# commu.net
KiCad netlist of a schematic drawn in Altium Designer
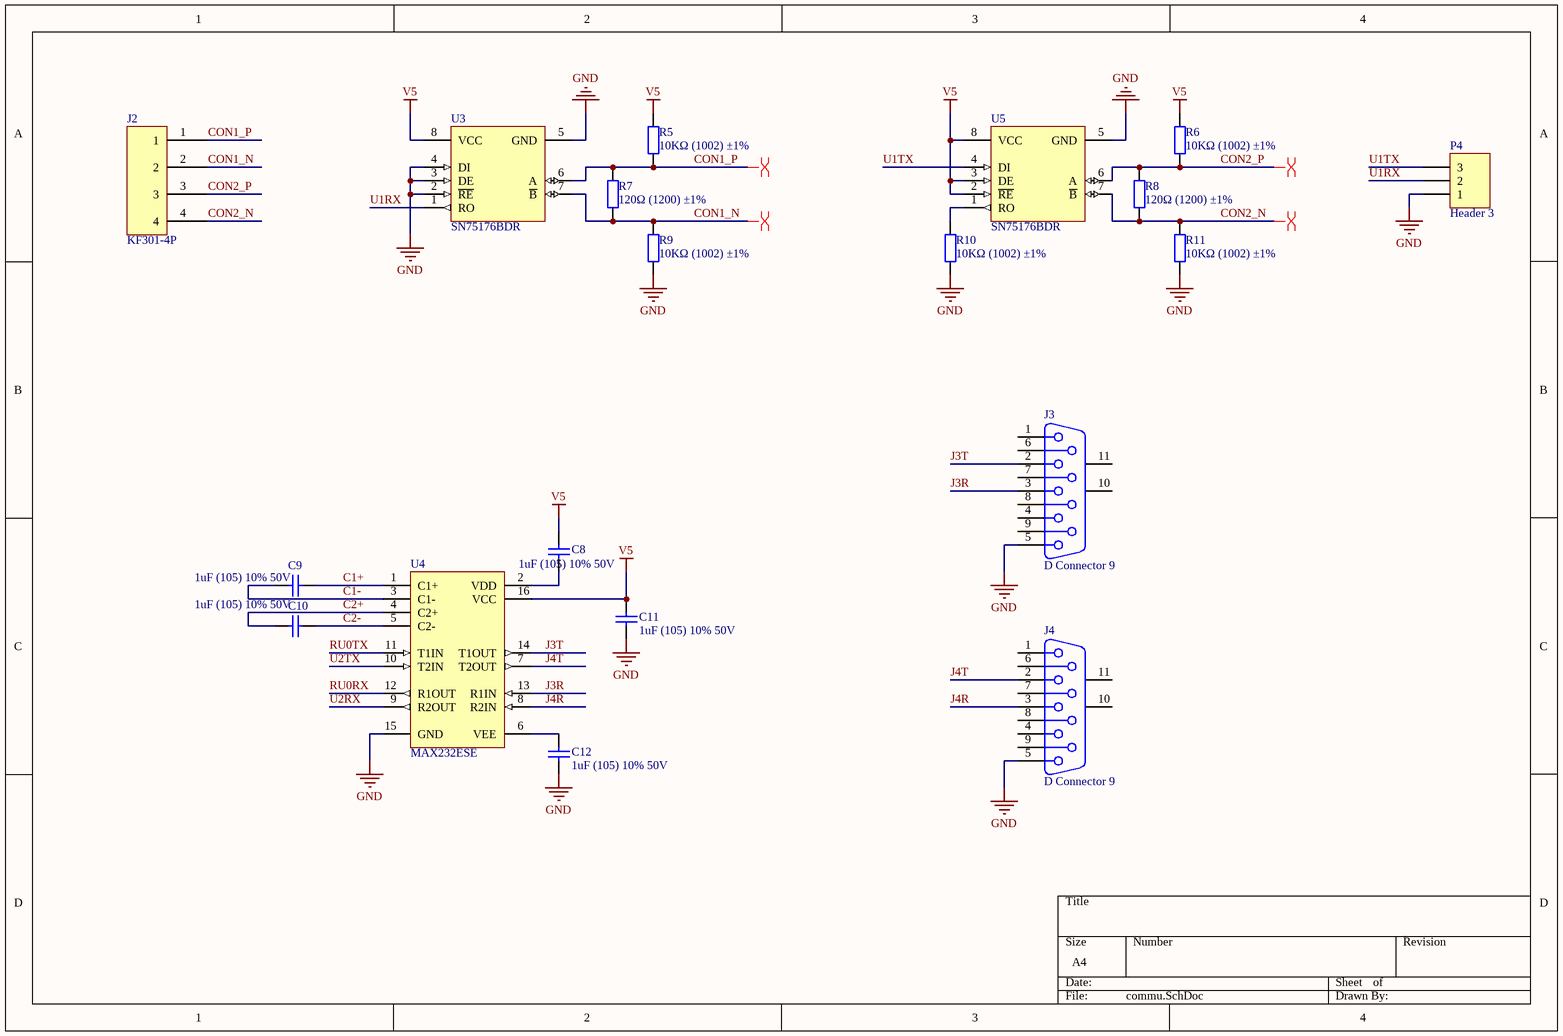
[diagram p0: commu.SchDoc]

(export (version "E")
  (design (tool "Eeschema 10.0.6"))
  (components
    (comp (ref "C8")
      (value "1uF (105) 10% 50V")
      (footprint "0603_C")
      (description "贴片电容")
      (libsource (lib "Miscellaneous Devices LC") (part "0603 1uF (105) 10% 50V"))
    )
    (comp (ref "C9")
      (value "1uF (105) 10% 50V")
      (footprint "0603_C")
      (description "贴片电容")
      (libsource (lib "Miscellaneous Devices LC") (part "0603 1uF (105) 10% 50V"))
    )
    (comp (ref "C10")
      (value "1uF (105) 10% 50V")
      (footprint "0603_C")
      (description "贴片电容")
      (libsource (lib "Miscellaneous Devices LC") (part "0603 1uF (105) 10% 50V"))
    )
    (comp (ref "C11")
      (value "1uF (105) 10% 50V")
      (footprint "0603_C")
      (description "贴片电容")
      (libsource (lib "Miscellaneous Devices LC") (part "0603 1uF (105) 10% 50V"))
    )
    (comp (ref "C12")
      (value "1uF (105) 10% 50V")
      (footprint "0603_C")
      (description "贴片电容")
      (libsource (lib "Miscellaneous Devices LC") (part "0603 1uF (105) 10% 50V"))
    )
    (comp (ref "J2") (value "KF301-4P") (footprint "KF301-4P") (libsource (lib "CHK-I") (part "KF301-4P")))
    (comp (ref "J3")
      (value "D Connector 9")
      (footprint "DSUB1.385-2H9")
      (description "Receptacle Assembly, 9 Position, Right Angle")
      (fields (field (name "PUBLISHER") "Altium Limited"))
      (libsource (lib "Miscellaneous Connectors") (part "D Connector 9"))
    )
    (comp (ref "J4")
      (value "D Connector 9")
      (footprint "DSUB1.385-2H9")
      (description "Receptacle Assembly, 9 Position, Right Angle")
      (fields (field (name "PUBLISHER") "Altium Limited"))
      (libsource (lib "Miscellaneous Connectors") (part "D Connector 9"))
    )
    (comp (ref "P4")
      (value "Header 3")
      (footprint "HDR1X3")
      (description "Header, 3-Pin")
      (fields (field (name "PUBLISHER") "Altium Limited"))
      (libsource (lib "Miscellaneous Connectors") (part "Header 3"))
    )
    (comp (ref "R5")
      (value "10KΩ (1002) ±1%")
      (footprint "0603_R")
      (description "贴片电阻")
      (libsource (lib "Miscellaneous Devices LC") (part "0603 10KΩ (1002) 1%"))
    )
    (comp (ref "R6")
      (value "10KΩ (1002) ±1%")
      (footprint "0603_R")
      (description "贴片电阻")
      (libsource (lib "Miscellaneous Devices LC") (part "0603 10KΩ (1002) 1%"))
    )
    (comp (ref "R7")
      (value "120Ω (1200) ±1%")
      (footprint "0603_R")
      (description "贴片电阻")
      (libsource (lib "Miscellaneous Devices LC") (part "0603 120Ω (1200) 1%"))
    )
    (comp (ref "R8")
      (value "120Ω (1200) ±1%")
      (footprint "0603_R")
      (description "贴片电阻")
      (libsource (lib "Miscellaneous Devices LC") (part "0603 120Ω (1200) 1%"))
    )
    (comp (ref "R9")
      (value "10KΩ (1002) ±1%")
      (footprint "0603_R")
      (description "贴片电阻")
      (libsource (lib "Miscellaneous Devices LC") (part "0603 10KΩ (1002) 1%"))
    )
    (comp (ref "R10")
      (value "10KΩ (1002) ±1%")
      (footprint "0603_R")
      (description "贴片电阻")
      (libsource (lib "Miscellaneous Devices LC") (part "0603 10KΩ (1002) 1%"))
    )
    (comp (ref "R11")
      (value "10KΩ (1002) ±1%")
      (footprint "0603_R")
      (description "贴片电阻")
      (libsource (lib "Miscellaneous Devices LC") (part "0603 10KΩ (1002) 1%"))
    )
    (comp (ref "U3")
      (value "SN75176BDR")
      (footprint "SOIC-8_150mil")
      (description "RS-485/RS-422")
      (libsource (lib "Miscellaneous Devices LC") (part "SN75176BDR_[C7063]"))
    )
    (comp (ref "U4")
      (value "MAX232ESE")
      (footprint "SOIC-16_150mil")
      (description "RS232")
      (libsource (lib "Miscellaneous Devices LC") (part "MAX232ESE_[C26860]"))
    )
    (comp (ref "U5")
      (value "SN75176BDR")
      (footprint "SOIC-8_150mil")
      (description "RS-485/RS-422")
      (libsource (lib "Miscellaneous Devices LC") (part "SN75176BDR_[C7063]"))
    )
  )
  (nets
    (net (code "1") (name "/C1+") (class "Default")
      (node (ref "C9") (pin "2") (pinfunction "2_2") (pintype "passive"))
      (node (ref "U4") (pin "1") (pinfunction "C1+_1") (pintype "passive"))
    )
    (net (code "2") (name "/C1-") (class "Default")
      (node (ref "C9") (pin "1") (pinfunction "1_1") (pintype "passive"))
      (node (ref "U4") (pin "3") (pinfunction "C1-_3") (pintype "passive"))
    )
    (net (code "3") (name "/C2+") (class "Default")
      (node (ref "C10") (pin "1") (pinfunction "1_1") (pintype "passive"))
      (node (ref "U4") (pin "4") (pinfunction "C2+_4") (pintype "passive"))
    )
    (net (code "4") (name "/C2-") (class "Default")
      (node (ref "C10") (pin "2") (pinfunction "2_2") (pintype "passive"))
      (node (ref "U4") (pin "5") (pinfunction "C2-_5") (pintype "passive"))
    )
    (net (code "5") (name "/CON1_N") (class "Default")
      (node (ref "J2") (pin "2") (pinfunction "2_2") (pintype "passive"))
      (node (ref "R7") (pin "1") (pinfunction "1_1") (pintype "passive"))
      (node (ref "R9") (pin "2") (pinfunction "2_2") (pintype "passive"))
      (node (ref "U3") (pin "7") (pinfunction "~{B}_7") (pintype "bidirectional"))
    )
    (net (code "6") (name "/CON1_P") (class "Default")
      (node (ref "J2") (pin "1") (pinfunction "1_1") (pintype "passive"))
      (node (ref "R5") (pin "1") (pinfunction "1_1") (pintype "passive"))
      (node (ref "R7") (pin "2") (pinfunction "2_2") (pintype "passive"))
      (node (ref "U3") (pin "6") (pinfunction "A_6") (pintype "bidirectional"))
    )
    (net (code "7") (name "/CON2_N") (class "Default")
      (node (ref "J2") (pin "4") (pinfunction "4_4") (pintype "passive"))
      (node (ref "R11") (pin "2") (pinfunction "2_2") (pintype "passive"))
      (node (ref "R8") (pin "1") (pinfunction "1_1") (pintype "passive"))
      (node (ref "U5") (pin "7") (pinfunction "~{B}_7") (pintype "bidirectional"))
    )
    (net (code "8") (name "/CON2_P") (class "Default")
      (node (ref "J2") (pin "3") (pinfunction "3_3") (pintype "passive"))
      (node (ref "R6") (pin "1") (pinfunction "1_1") (pintype "passive"))
      (node (ref "R8") (pin "2") (pinfunction "2_2") (pintype "passive"))
      (node (ref "U5") (pin "6") (pinfunction "A_6") (pintype "bidirectional"))
    )
    (net (code "9") (name "/J3R") (class "Default")
      (node (ref "J3") (pin "3") (pinfunction "3_3") (pintype "passive"))
      (node (ref "U4") (pin "13") (pinfunction "R1IN_13") (pintype "input"))
    )
    (net (code "10") (name "/J3T") (class "Default")
      (node (ref "J3") (pin "2") (pinfunction "2_2") (pintype "passive"))
      (node (ref "U4") (pin "14") (pinfunction "T1OUT_14") (pintype "output"))
    )
    (net (code "11") (name "/J4R") (class "Default")
      (node (ref "J4") (pin "3") (pinfunction "3_3") (pintype "passive"))
      (node (ref "U4") (pin "8") (pinfunction "R2IN_8") (pintype "input"))
    )
    (net (code "12") (name "/J4T") (class "Default")
      (node (ref "J4") (pin "2") (pinfunction "2_2") (pintype "passive"))
      (node (ref "U4") (pin "7") (pinfunction "T2OUT_7") (pintype "output"))
    )
    (net (code "13") (name "/RU0RX") (class "Default")
      (node (ref "U4") (pin "12") (pinfunction "R1OUT_12") (pintype "output"))
    )
    (net (code "14") (name "/RU0TX") (class "Default")
      (node (ref "U4") (pin "11") (pinfunction "T1IN_11") (pintype "input"))
    )
    (net (code "15") (name "/U1RX") (class "Default")
      (node (ref "P4") (pin "2") (pinfunction "2_2") (pintype "passive"))
      (node (ref "U3") (pin "1") (pinfunction "RO_1") (pintype "output"))
    )
    (net (code "16") (name "/U1TX") (class "Default")
      (node (ref "P4") (pin "3") (pinfunction "3_3") (pintype "passive"))
      (node (ref "U5") (pin "4") (pinfunction "DI_4") (pintype "input"))
    )
    (net (code "17") (name "/U2RX") (class "Default")
      (node (ref "U4") (pin "9") (pinfunction "R2OUT_9") (pintype "output"))
    )
    (net (code "18") (name "/U2TX") (class "Default")
      (node (ref "U4") (pin "10") (pinfunction "T2IN_10") (pintype "input"))
    )
    (net (code "19") (name "GND") (class "Default")
      (node (ref "C11") (pin "1") (pinfunction "1_1") (pintype "passive"))
      (node (ref "C12") (pin "1") (pinfunction "1_1") (pintype "passive"))
      (node (ref "J3") (pin "5") (pinfunction "5_5") (pintype "passive"))
      (node (ref "J4") (pin "5") (pinfunction "5_5") (pintype "passive"))
      (node (ref "P4") (pin "1") (pinfunction "1_1") (pintype "passive"))
      (node (ref "R10") (pin "1") (pinfunction "1_1") (pintype "passive"))
      (node (ref "R11") (pin "1") (pinfunction "1_1") (pintype "passive"))
      (node (ref "R9") (pin "1") (pinfunction "1_1") (pintype "passive"))
      (node (ref "U3") (pin "2") (pinfunction "~{RE}_2") (pintype "input"))
      (node (ref "U3") (pin "3") (pinfunction "DE_3") (pintype "input"))
      (node (ref "U3") (pin "4") (pinfunction "DI_4") (pintype "input"))
      (node (ref "U3") (pin "5") (pinfunction "GND_5") (pintype "power_in"))
      (node (ref "U4") (pin "15") (pinfunction "GND_15") (pintype "power_in"))
      (node (ref "U5") (pin "5") (pinfunction "GND_5") (pintype "power_in"))
    )
    (net (code "20") (name "Net-(U4-VDD)") (class "Default")
      (node (ref "C8") (pin "1") (pinfunction "1_1") (pintype "passive"))
      (node (ref "U4") (pin "2") (pinfunction "VDD_2") (pintype "power_in"))
    )
    (net (code "21") (name "Net-(U4-VEE)") (class "Default")
      (node (ref "C12") (pin "2") (pinfunction "2_2") (pintype "passive"))
      (node (ref "U4") (pin "6") (pinfunction "VEE_6") (pintype "power_in"))
    )
    (net (code "22") (name "Net-(U5-RO)") (class "Default")
      (node (ref "R10") (pin "2") (pinfunction "2_2") (pintype "passive"))
      (node (ref "U5") (pin "1") (pinfunction "RO_1") (pintype "output"))
    )
    (net (code "23") (name "V5") (class "Default")
      (node (ref "C11") (pin "2") (pinfunction "2_2") (pintype "passive"))
      (node (ref "C8") (pin "2") (pinfunction "2_2") (pintype "passive"))
      (node (ref "R5") (pin "2") (pinfunction "2_2") (pintype "passive"))
      (node (ref "R6") (pin "2") (pinfunction "2_2") (pintype "passive"))
      (node (ref "U3") (pin "8") (pinfunction "VCC_8") (pintype "power_in"))
      (node (ref "U4") (pin "16") (pinfunction "VCC_16") (pintype "power_in"))
      (node (ref "U5") (pin "2") (pinfunction "~{RE}_2") (pintype "input"))
      (node (ref "U5") (pin "3") (pinfunction "DE_3") (pintype "input"))
      (node (ref "U5") (pin "8") (pinfunction "VCC_8") (pintype "power_in"))
    )
    (net (code "24") (name "unconnected-(J3-MH1-Pad10)") (class "Default")
      (node (ref "J3") (pin "10") (pinfunction "MH1_10") (pintype "passive"))
    )
    (net (code "25") (name "unconnected-(J3-MH2-Pad11)") (class "Default")
      (node (ref "J3") (pin "11") (pinfunction "MH2_11") (pintype "passive"))
    )
    (net (code "26") (name "unconnected-(J3-Pad1)") (class "Default")
      (node (ref "J3") (pin "1") (pinfunction "1_1") (pintype "passive"))
    )
    (net (code "27") (name "unconnected-(J3-Pad4)") (class "Default")
      (node (ref "J3") (pin "4") (pinfunction "4_4") (pintype "passive"))
    )
    (net (code "28") (name "unconnected-(J3-Pad6)") (class "Default")
      (node (ref "J3") (pin "6") (pinfunction "6_6") (pintype "passive"))
    )
    (net (code "29") (name "unconnected-(J3-Pad7)") (class "Default")
      (node (ref "J3") (pin "7") (pinfunction "7_7") (pintype "passive"))
    )
    (net (code "30") (name "unconnected-(J3-Pad8)") (class "Default")
      (node (ref "J3") (pin "8") (pinfunction "8_8") (pintype "passive"))
    )
    (net (code "31") (name "unconnected-(J3-Pad9)") (class "Default")
      (node (ref "J3") (pin "9") (pinfunction "9_9") (pintype "passive"))
    )
    (net (code "32") (name "unconnected-(J4-MH1-Pad10)") (class "Default")
      (node (ref "J4") (pin "10") (pinfunction "MH1_10") (pintype "passive"))
    )
    (net (code "33") (name "unconnected-(J4-MH2-Pad11)") (class "Default")
      (node (ref "J4") (pin "11") (pinfunction "MH2_11") (pintype "passive"))
    )
    (net (code "34") (name "unconnected-(J4-Pad1)") (class "Default")
      (node (ref "J4") (pin "1") (pinfunction "1_1") (pintype "passive"))
    )
    (net (code "35") (name "unconnected-(J4-Pad4)") (class "Default")
      (node (ref "J4") (pin "4") (pinfunction "4_4") (pintype "passive"))
    )
    (net (code "36") (name "unconnected-(J4-Pad6)") (class "Default")
      (node (ref "J4") (pin "6") (pinfunction "6_6") (pintype "passive"))
    )
    (net (code "37") (name "unconnected-(J4-Pad7)") (class "Default")
      (node (ref "J4") (pin "7") (pinfunction "7_7") (pintype "passive"))
    )
    (net (code "38") (name "unconnected-(J4-Pad8)") (class "Default")
      (node (ref "J4") (pin "8") (pinfunction "8_8") (pintype "passive"))
    )
    (net (code "39") (name "unconnected-(J4-Pad9)") (class "Default")
      (node (ref "J4") (pin "9") (pinfunction "9_9") (pintype "passive"))
    )
  )
)
